# plan.net
KiCad netlist of a schematic drawn in EAGLE
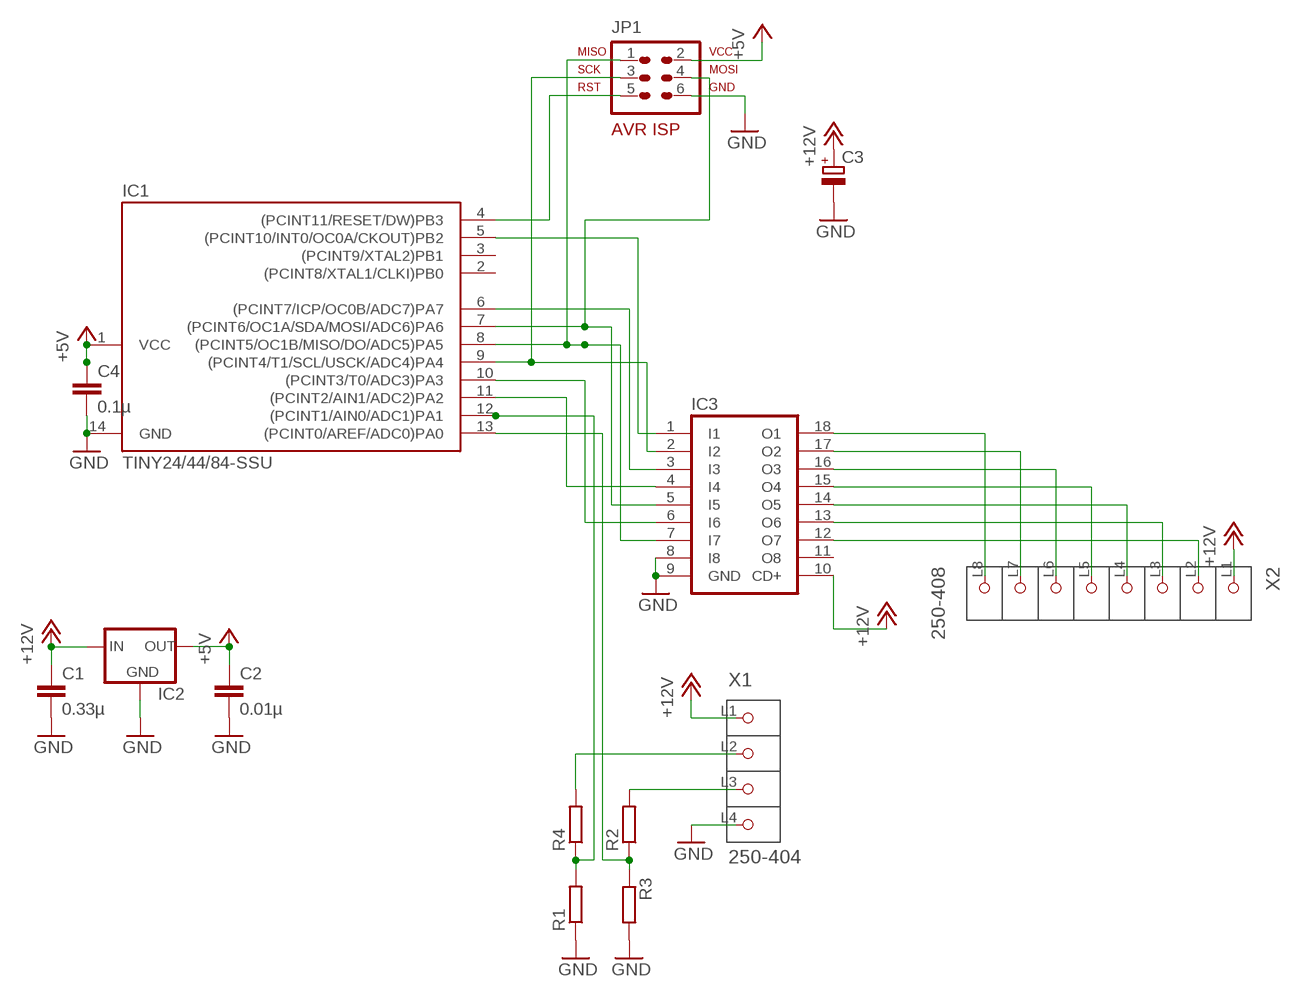
[diagram p0: schematic, sheet 1]

(export (version "E")
  (design (tool "Eeschema 10.0.6"))
  (components
    (comp (ref "C1")
      (value "0.33µ")
      (footprint "eagle-import:C025-025X050")
      (libsource (lib "eagle-import") (part "C-EU025-025X050"))
    )
    (comp (ref "C2")
      (value "0.01µ")
      (footprint "eagle-import:C025-025X050")
      (libsource (lib "eagle-import") (part "C-EU025-025X050"))
    )
    (comp (ref "C3")
      (value "CPOL-EUSANYO_B")
      (footprint "eagle-import:SANYO-OSCON_B")
      (libsource (lib "eagle-import") (part "CPOL-EUSANYO_B"))
    )
    (comp (ref "C4")
      (value "0.1µ")
      (footprint "eagle-import:C025-030X050")
      (libsource (lib "eagle-import") (part "C-EU025-030X050"))
    )
    (comp (ref "IC1")
      (value "TINY24/44/84-SSU")
      (footprint "eagle-import:SOIC14")
      (libsource (lib "eagle-import") (part "TINY24/44/84-SSU"))
    )
    (comp (ref "IC2")
      (value "78LXX")
      (footprint "eagle-import:78LXX")
      (libsource (lib "eagle-import") (part "78LXX"))
    )
    (comp (ref "IC3")
      (value "ULN2803ASMD")
      (footprint "eagle-import:SO18W")
      (libsource (lib "eagle-import") (part "ULN2803ASMD"))
    )
    (comp (ref "JP1")
      (value "AVR-ISP-6VERT")
      (footprint "eagle-import:AVR-ISP-6")
      (libsource (lib "eagle-import") (part "AVR-ISP-6VERT"))
    )
    (comp (ref "R1")
      (value "R-EU_0204/2V")
      (footprint "eagle-import:0204V")
      (libsource (lib "eagle-import") (part "R-EU_0204/2V"))
    )
    (comp (ref "R2")
      (value "R-EU_0204/2V")
      (footprint "eagle-import:0204V")
      (libsource (lib "eagle-import") (part "R-EU_0204/2V"))
    )
    (comp (ref "R3")
      (value "R-EU_0204/2V")
      (footprint "eagle-import:0204V")
      (libsource (lib "eagle-import") (part "R-EU_0204/2V"))
    )
    (comp (ref "R4")
      (value "R-EU_0207/10")
      (footprint "eagle-import:0207_10")
      (libsource (lib "eagle-import") (part "R-EU_0207/10"))
    )
    (comp (ref "X1")
      (value "250-404")
      (footprint "eagle-import:P-250-404")
      (libsource (lib "eagle-import") (part "250-404"))
    )
    (comp (ref "X2")
      (value "250-408")
      (footprint "eagle-import:P-250-408")
      (libsource (lib "eagle-import") (part "250-408"))
    )
  )
  (nets
    (net (code "1") (name "+5V") (class "Default")
      (node (ref "C2") (pin "1") (pinfunction "1_1") (pintype "passive"))
      (node (ref "C4") (pin "1") (pinfunction "1_1") (pintype "passive"))
      (node (ref "IC1") (pin "1") (pinfunction "VCC_1") (pintype "power_in"))
      (node (ref "IC2") (pin "OUT") (pinfunction "OUT_OUT") (pintype "passive"))
      (node (ref "JP1") (pin "2") (pinfunction "2_2") (pintype "passive"))
    )
    (net (code "2") (name "+12V") (class "Default")
      (node (ref "C1") (pin "1") (pinfunction "1_1") (pintype "passive"))
      (node (ref "C3") (pin "+") (pinfunction "+_+") (pintype "passive"))
      (node (ref "IC2") (pin "IN") (pinfunction "IN_IN") (pintype "input"))
      (node (ref "IC3") (pin "10") (pinfunction "CD+_10") (pintype "passive"))
      (node (ref "X1") (pin "L1") (pinfunction "P1_L1") (pintype "bidirectional"))
      (node (ref "X2") (pin "L1") (pinfunction "P1_L1") (pintype "bidirectional"))
    )
    (net (code "3") (name "GND") (class "Default")
      (node (ref "C1") (pin "2") (pinfunction "2_2") (pintype "passive"))
      (node (ref "C2") (pin "2") (pinfunction "2_2") (pintype "passive"))
      (node (ref "C3") (pin "-") (pinfunction "-_-") (pintype "passive"))
      (node (ref "C4") (pin "2") (pinfunction "2_2") (pintype "passive"))
      (node (ref "IC1") (pin "14") (pinfunction "GND_14") (pintype "power_in"))
      (node (ref "IC2") (pin "GND") (pinfunction "GND_GND") (pintype "input"))
      (node (ref "IC3") (pin "8") (pinfunction "I8_8") (pintype "input"))
      (node (ref "IC3") (pin "9") (pinfunction "GND_9") (pintype "power_in"))
      (node (ref "JP1") (pin "6") (pinfunction "6_6") (pintype "passive"))
      (node (ref "R1") (pin "1") (pinfunction "1_1") (pintype "passive"))
      (node (ref "R3") (pin "2") (pinfunction "2_2") (pintype "passive"))
      (node (ref "X1") (pin "L4") (pinfunction "P4_L4") (pintype "bidirectional"))
    )
    (net (code "4") (name "Net-(IC1-(PCINT0{slash}AREF{slash}ADC0)PA0)") (class "Default")
      (node (ref "IC1") (pin "13") (pinfunction "(PCINT0/AREF/ADC0)PA0_13") (pintype "bidirectional"))
      (node (ref "R2") (pin "1") (pinfunction "1_1") (pintype "passive"))
      (node (ref "R3") (pin "1") (pinfunction "1_1") (pintype "passive"))
    )
    (net (code "5") (name "Net-(IC1-(PCINT1{slash}AIN0{slash}ADC1)PA1)") (class "Default")
      (node (ref "IC1") (pin "12") (pinfunction "(PCINT1/AIN0/ADC1)PA1_12") (pintype "bidirectional"))
      (node (ref "R1") (pin "2") (pinfunction "2_2") (pintype "passive"))
      (node (ref "R4") (pin "1") (pinfunction "1_1") (pintype "passive"))
    )
    (net (code "6") (name "Net-(IC1-(PCINT2{slash}AIN1{slash}ADC2)PA2)") (class "Default")
      (node (ref "IC1") (pin "11") (pinfunction "(PCINT2/AIN1/ADC2)PA2_11") (pintype "bidirectional"))
      (node (ref "IC3") (pin "4") (pinfunction "I4_4") (pintype "input"))
    )
    (net (code "7") (name "Net-(IC1-(PCINT3{slash}T0{slash}ADC3)PA3)") (class "Default")
      (node (ref "IC1") (pin "10") (pinfunction "(PCINT3/T0/ADC3)PA3_10") (pintype "bidirectional"))
      (node (ref "IC3") (pin "6") (pinfunction "I6_6") (pintype "input"))
    )
    (net (code "8") (name "Net-(IC1-(PCINT4{slash}T1{slash}SCL{slash}USCK{slash}ADC4)PA4)") (class "Default")
      (node (ref "IC1") (pin "9") (pinfunction "(PCINT4/T1/SCL/USCK/ADC4)PA4_9") (pintype "bidirectional"))
      (node (ref "IC3") (pin "2") (pinfunction "I2_2") (pintype "input"))
      (node (ref "JP1") (pin "3") (pinfunction "3_3") (pintype "passive"))
    )
    (net (code "9") (name "Net-(IC1-(PCINT5{slash}OC1B{slash}MISO{slash}DO{slash}ADC5)PA5)") (class "Default")
      (node (ref "IC1") (pin "8") (pinfunction "(PCINT5/OC1B/MISO/DO/ADC5)PA5_8") (pintype "bidirectional"))
      (node (ref "IC3") (pin "7") (pinfunction "I7_7") (pintype "input"))
      (node (ref "JP1") (pin "1") (pinfunction "1_1") (pintype "passive"))
    )
    (net (code "10") (name "Net-(IC1-(PCINT6{slash}OC1A{slash}SDA{slash}MOSI{slash}ADC6)PA6)") (class "Default")
      (node (ref "IC1") (pin "7") (pinfunction "(PCINT6/OC1A/SDA/MOSI/ADC6)PA6_7") (pintype "bidirectional"))
      (node (ref "IC3") (pin "5") (pinfunction "I5_5") (pintype "input"))
      (node (ref "JP1") (pin "4") (pinfunction "4_4") (pintype "passive"))
    )
    (net (code "11") (name "Net-(IC1-(PCINT7{slash}ICP{slash}OC0B{slash}ADC7)PA7)") (class "Default")
      (node (ref "IC1") (pin "6") (pinfunction "(PCINT7/ICP/OC0B/ADC7)PA7_6") (pintype "bidirectional"))
      (node (ref "IC3") (pin "3") (pinfunction "I3_3") (pintype "input"))
    )
    (net (code "12") (name "Net-(IC1-(PCINT10{slash}INT0{slash}OC0A{slash}CKOUT)PB2)") (class "Default")
      (node (ref "IC1") (pin "5") (pinfunction "(PCINT10/INT0/OC0A/CKOUT)PB2_5") (pintype "bidirectional"))
      (node (ref "IC3") (pin "1") (pinfunction "I1_1") (pintype "input"))
    )
    (net (code "13") (name "Net-(IC1-(PCINT11{slash}RESET{slash}DW)PB3)") (class "Default")
      (node (ref "IC1") (pin "4") (pinfunction "(PCINT11/RESET/DW)PB3_4") (pintype "bidirectional"))
      (node (ref "JP1") (pin "5") (pinfunction "5_5") (pintype "passive"))
    )
    (net (code "14") (name "Net-(IC3-O1)") (class "Default")
      (node (ref "IC3") (pin "18") (pinfunction "O1_18") (pintype "open_collector"))
      (node (ref "X2") (pin "L8") (pinfunction "P8_L8") (pintype "bidirectional"))
    )
    (net (code "15") (name "Net-(IC3-O2)") (class "Default")
      (node (ref "IC3") (pin "17") (pinfunction "O2_17") (pintype "open_collector"))
      (node (ref "X2") (pin "L7") (pinfunction "P7_L7") (pintype "bidirectional"))
    )
    (net (code "16") (name "Net-(IC3-O3)") (class "Default")
      (node (ref "IC3") (pin "16") (pinfunction "O3_16") (pintype "open_collector"))
      (node (ref "X2") (pin "L6") (pinfunction "P6_L6") (pintype "bidirectional"))
    )
    (net (code "17") (name "Net-(IC3-O4)") (class "Default")
      (node (ref "IC3") (pin "15") (pinfunction "O4_15") (pintype "open_collector"))
      (node (ref "X2") (pin "L5") (pinfunction "P5_L5") (pintype "bidirectional"))
    )
    (net (code "18") (name "Net-(IC3-O5)") (class "Default")
      (node (ref "IC3") (pin "14") (pinfunction "O5_14") (pintype "open_collector"))
      (node (ref "X2") (pin "L4") (pinfunction "P4_L4") (pintype "bidirectional"))
    )
    (net (code "19") (name "Net-(IC3-O6)") (class "Default")
      (node (ref "IC3") (pin "13") (pinfunction "O6_13") (pintype "open_collector"))
      (node (ref "X2") (pin "L3") (pinfunction "P3_L3") (pintype "bidirectional"))
    )
    (net (code "20") (name "Net-(IC3-O7)") (class "Default")
      (node (ref "IC3") (pin "12") (pinfunction "O7_12") (pintype "open_collector"))
      (node (ref "X2") (pin "L2") (pinfunction "P2_L2") (pintype "bidirectional"))
    )
    (net (code "21") (name "Net-(X1-P2)") (class "Default")
      (node (ref "R4") (pin "2") (pinfunction "2_2") (pintype "passive"))
      (node (ref "X1") (pin "L2") (pinfunction "P2_L2") (pintype "bidirectional"))
    )
    (net (code "22") (name "Net-(X1-P3)") (class "Default")
      (node (ref "R2") (pin "2") (pinfunction "2_2") (pintype "passive"))
      (node (ref "X1") (pin "L3") (pinfunction "P3_L3") (pintype "bidirectional"))
    )
    (net (code "23") (name "unconnected-(IC1-(PCINT8{slash}XTAL1{slash}CLKI)PB0-Pad2)") (class "Default")
      (node (ref "IC1") (pin "2") (pinfunction "(PCINT8/XTAL1/CLKI)PB0_2") (pintype "bidirectional"))
    )
    (net (code "24") (name "unconnected-(IC1-(PCINT9{slash}XTAL2)PB1-Pad3)") (class "Default")
      (node (ref "IC1") (pin "3") (pinfunction "(PCINT9/XTAL2)PB1_3") (pintype "bidirectional"))
    )
    (net (code "25") (name "unconnected-(IC3-O8-Pad11)") (class "Default")
      (node (ref "IC3") (pin "11") (pinfunction "O8_11") (pintype "open_collector"))
    )
  )
)
